# controller_v4.net
KiCad netlist of a schematic drawn in EAGLE
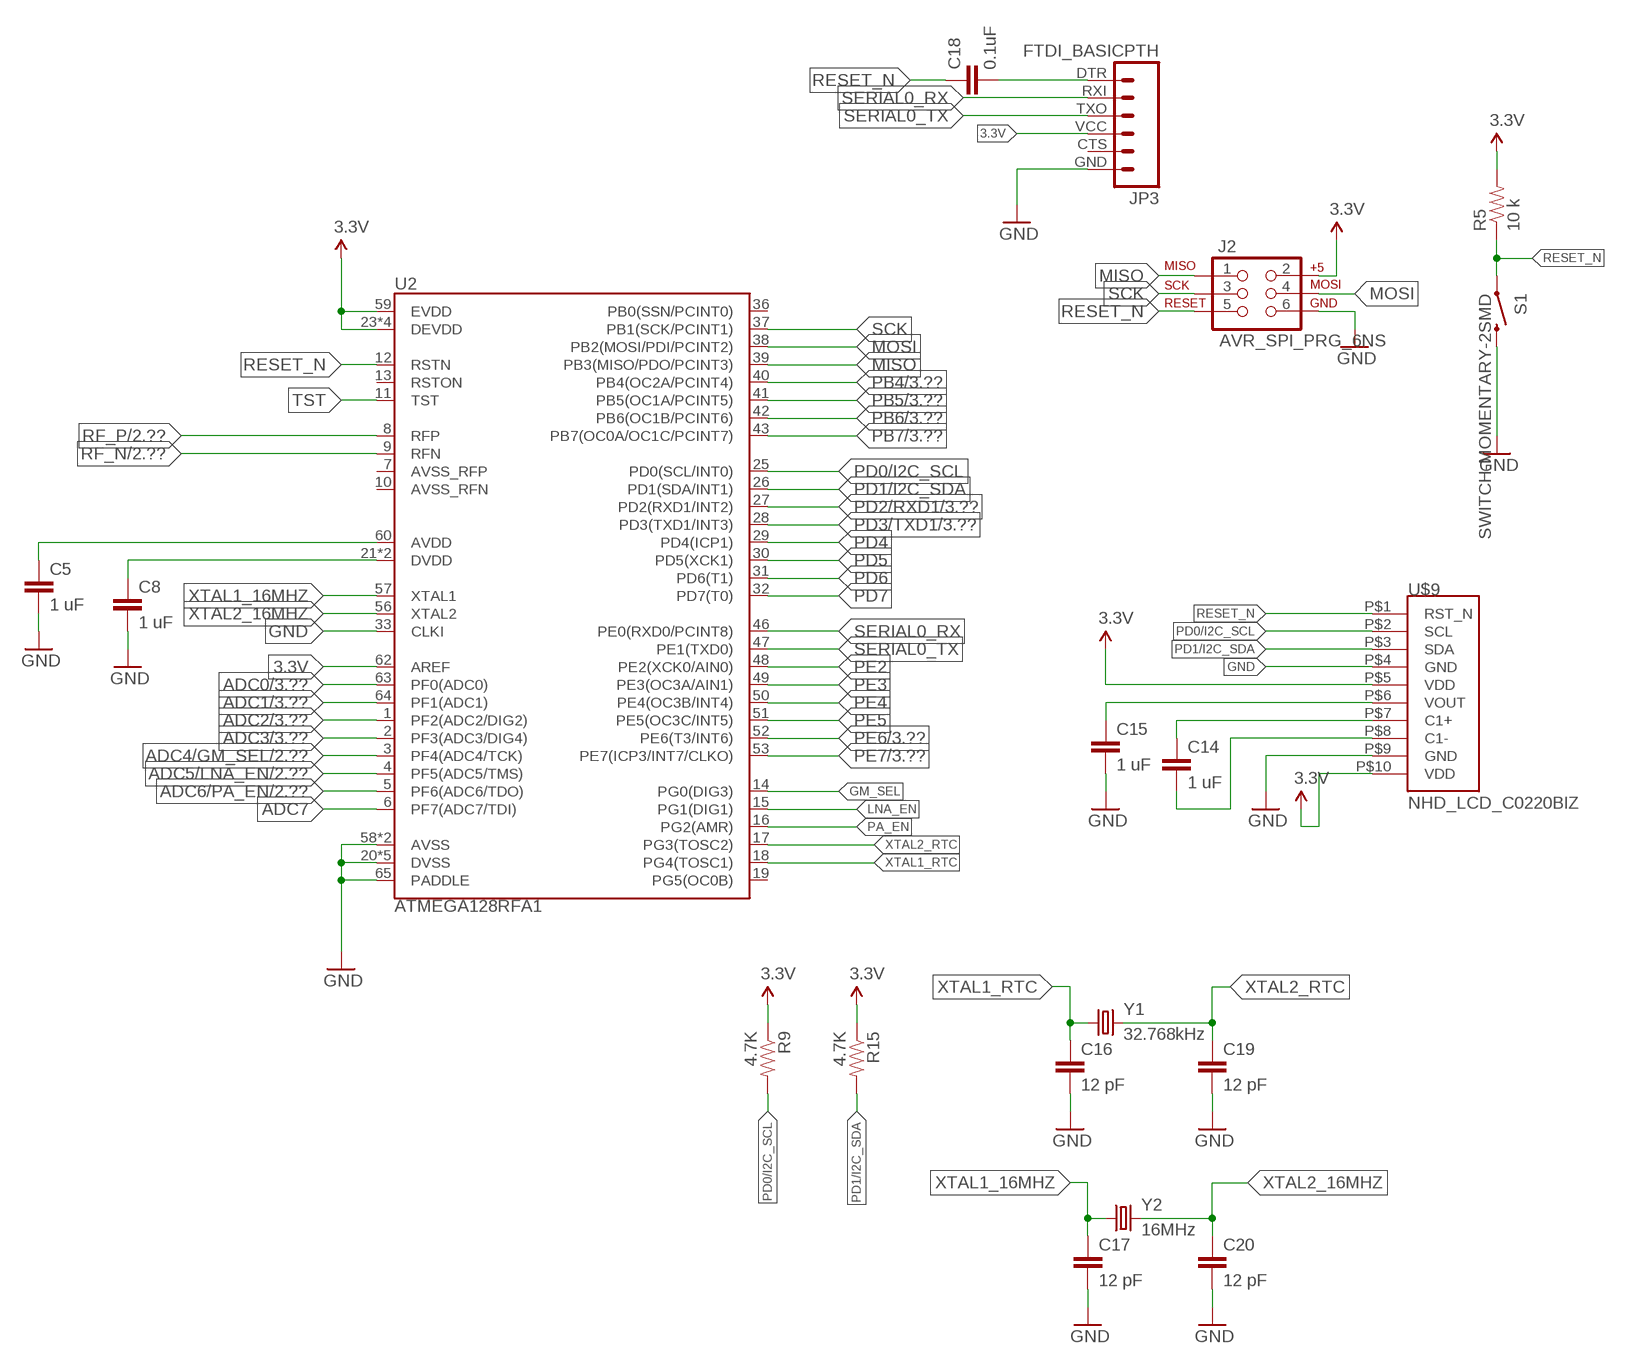
[diagram p0: schematic, sheet 1]
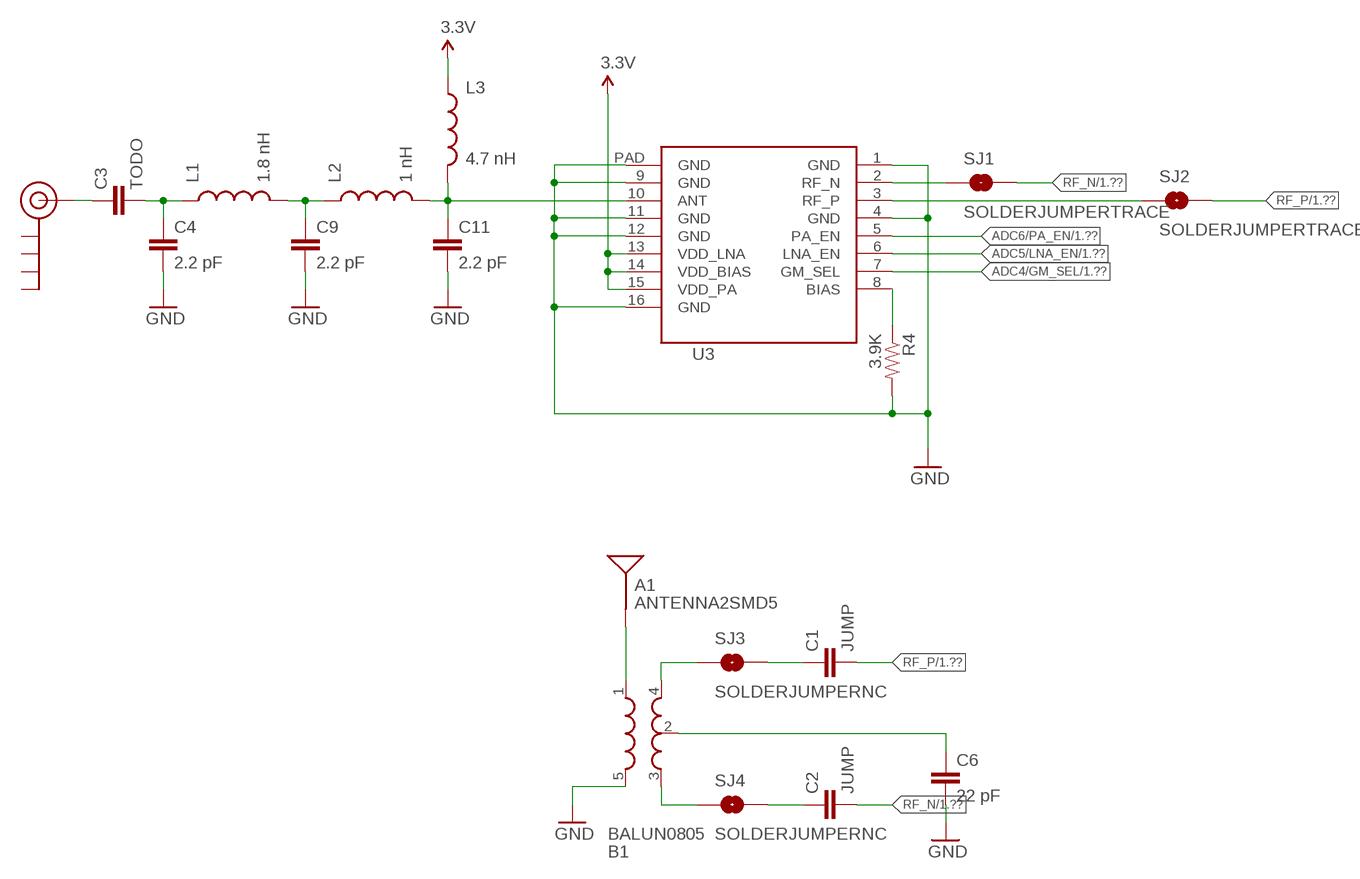
[diagram p1: schematic, sheet 2]
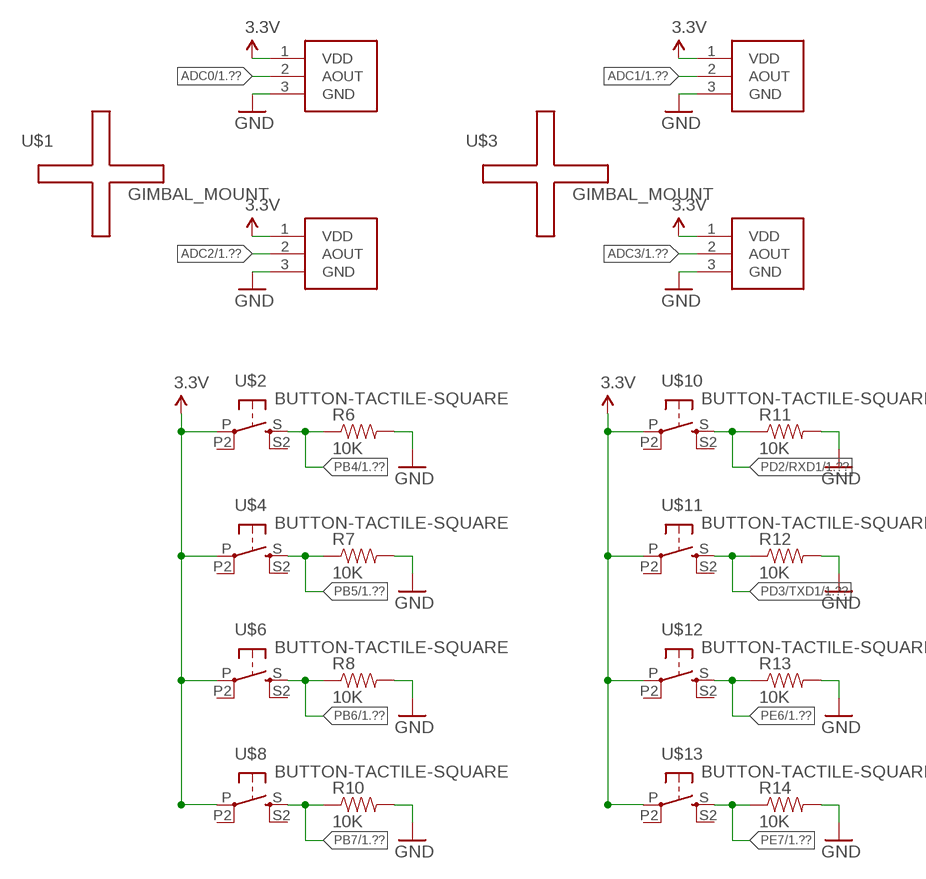
[diagram p2: schematic, sheet 3]
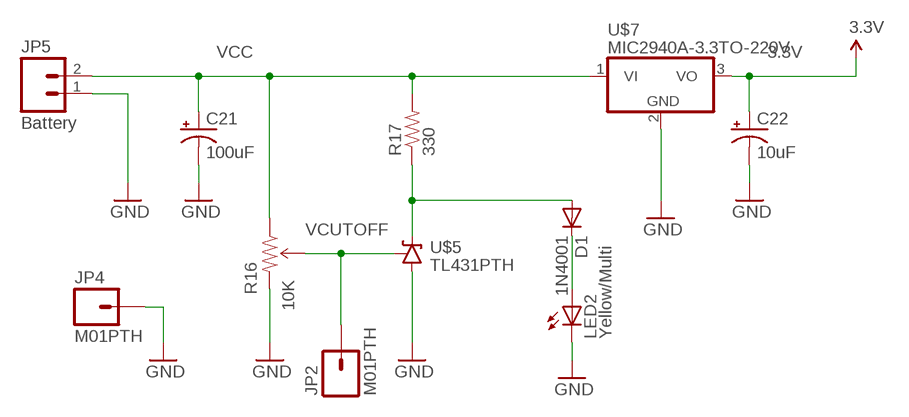
[diagram p3: schematic, sheet 4]

(export (version "E")
  (design (tool "Eeschema 10.0.6"))
  (components
    (comp (ref "A1")
      (value "ANTENNA2SMD5")
      (footprint "eagle-import:ANTENNA-CHIP5")
      (libsource (lib "eagle-import") (part "ANTENNA2SMD5"))
    )
    (comp (ref "B1")
      (value "BALUN0805")
      (footprint "eagle-import:BALUN")
      (libsource (lib "eagle-import") (part "BALUN0805"))
    )
    (comp (ref "C1")
      (value "JUMP")
      (footprint "eagle-import:0805")
      (libsource (lib "eagle-import") (part "CAP0805"))
    )
    (comp (ref "C2")
      (value "JUMP")
      (footprint "eagle-import:0805")
      (libsource (lib "eagle-import") (part "CAP0805"))
    )
    (comp (ref "C3")
      (value "TODO")
      (footprint "eagle-import:0805")
      (libsource (lib "eagle-import") (part "CAP0805"))
    )
    (comp (ref "C4")
      (value "2.2 pF")
      (footprint "eagle-import:0805")
      (libsource (lib "eagle-import") (part "CAP0805"))
    )
    (comp (ref "C6")
      (value "22 pF")
      (footprint "eagle-import:0805")
      (libsource (lib "eagle-import") (part "CAP0805"))
    )
    (comp (ref "C9")
      (value "2.2 pF")
      (footprint "eagle-import:0805")
      (libsource (lib "eagle-import") (part "CAP0805"))
    )
    (comp (ref "C11")
      (value "2.2 pF")
      (footprint "eagle-import:0805")
      (libsource (lib "eagle-import") (part "CAP0805"))
    )
    (comp (ref "J$1")
      (value "SMA_EDGE")
      (footprint "eagle-import:SMA-EDGE")
      (libsource (lib "eagle-import") (part "SMA_EDGE"))
    )
    (comp (ref "L1")
      (value "1.8 nH")
      (footprint "eagle-import:0805")
      (libsource (lib "eagle-import") (part "INDUCTOR0805"))
    )
    (comp (ref "L2")
      (value "1 nH")
      (footprint "eagle-import:0805")
      (libsource (lib "eagle-import") (part "INDUCTOR0805"))
    )
    (comp (ref "L3")
      (value "4.7 nH")
      (footprint "eagle-import:0805")
      (libsource (lib "eagle-import") (part "INDUCTOR0805"))
    )
    (comp (ref "R4")
      (value "3.9K")
      (footprint "eagle-import:0805")
      (libsource (lib "eagle-import") (part "RESISTOR0805-RES"))
    )
    (comp (ref "SJ1")
      (value "SOLDERJUMPERTRACE")
      (footprint "eagle-import:SJ_2S-TRACE")
      (libsource (lib "eagle-import") (part "SOLDERJUMPERTRACE"))
    )
    (comp (ref "SJ2")
      (value "SOLDERJUMPERTRACE")
      (footprint "eagle-import:SJ_2S-TRACE")
      (libsource (lib "eagle-import") (part "SOLDERJUMPERTRACE"))
    )
    (comp (ref "SJ3")
      (value "SOLDERJUMPERNC")
      (footprint "eagle-import:SJ_2S")
      (libsource (lib "eagle-import") (part "SOLDERJUMPERNC"))
    )
    (comp (ref "SJ4")
      (value "SOLDERJUMPERNC")
      (footprint "eagle-import:SJ_2S")
      (libsource (lib "eagle-import") (part "SOLDERJUMPERNC"))
    )
    (comp (ref "U3")
      (value "RF_AMPLIFIER")
      (footprint "eagle-import:QFN65P400X400X100-17N")
      (libsource (lib "eagle-import") (part "CC2592QF"))
    )
    (comp (ref "C21")
      (value "100uF")
      (footprint "eagle-import:E3,5-8")
      (libsource (lib "eagle-import") (part "CPOL-USE3.5-8"))
    )
    (comp (ref "C22")
      (value "10uF")
      (footprint "eagle-import:E2,5-5")
      (libsource (lib "eagle-import") (part "CPOL-USE2.5-5"))
    )
    (comp (ref "D1")
      (value "1N4001")
      (footprint "eagle-import:DO41-10")
      (libsource (lib "eagle-import") (part "1N4004"))
    )
    (comp (ref "JP2")
      (value "M01PTH")
      (footprint "eagle-import:1X01")
      (libsource (lib "eagle-import") (part "M01PTH"))
    )
    (comp (ref "JP4")
      (value "M01PTH")
      (footprint "eagle-import:1X01")
      (libsource (lib "eagle-import") (part "M01PTH"))
    )
    (comp (ref "JP5")
      (value "Battery")
      (footprint "eagle-import:1X02")
      (libsource (lib "eagle-import") (part "M02PTH"))
    )
    (comp (ref "LED2")
      (value "Yellow/Multi")
      (footprint "eagle-import:LED5MM")
      (libsource (lib "eagle-import") (part "LED5MM"))
    )
    (comp (ref "R16")
      (value "10K")
      (footprint "eagle-import:3386U")
      (libsource (lib "eagle-import") (part "TRIMPOT-PTH-KNOB"))
    )
    (comp (ref "R17")
      (value "330")
      (footprint "eagle-import:AXIAL-0.3")
      (libsource (lib "eagle-import") (part "SparkFun_RESISTORAXIAL-0.3"))
    )
    (comp (ref "U$5")
      (value "TL431PTH")
      (footprint "eagle-import:TO-92")
      (libsource (lib "eagle-import") (part "TL431PTH"))
    )
    (comp (ref "U$7")
      (value "MIC2940A-3.3TO-220V")
      (footprint "eagle-import:TO-220V")
      (libsource (lib "eagle-import") (part "MIC2940A-3.3TO-220V"))
    )
    (comp (ref "J3")
      (value "GIMBAL_3PIN")
      (footprint "eagle-import:JST-3-PTH")
      (libsource (lib "eagle-import") (part "GIMBAL_3PIN"))
    )
    (comp (ref "J4")
      (value "GIMBAL_3PIN")
      (footprint "eagle-import:JST-3-PTH")
      (libsource (lib "eagle-import") (part "GIMBAL_3PIN"))
    )
    (comp (ref "J5")
      (value "GIMBAL_3PIN")
      (footprint "eagle-import:JST-3-PTH")
      (libsource (lib "eagle-import") (part "GIMBAL_3PIN"))
    )
    (comp (ref "J6")
      (value "GIMBAL_3PIN")
      (footprint "eagle-import:JST-3-PTH")
      (libsource (lib "eagle-import") (part "GIMBAL_3PIN"))
    )
    (comp (ref "R6")
      (value "10K")
      (footprint "eagle-import:0805")
      (libsource (lib "eagle-import") (part "RESISTOR0805-RES"))
    )
    (comp (ref "R7")
      (value "10K")
      (footprint "eagle-import:0805")
      (libsource (lib "eagle-import") (part "RESISTOR0805-RES"))
    )
    (comp (ref "R8")
      (value "10K")
      (footprint "eagle-import:0805")
      (libsource (lib "eagle-import") (part "RESISTOR0805-RES"))
    )
    (comp (ref "R10")
      (value "10K")
      (footprint "eagle-import:0805")
      (libsource (lib "eagle-import") (part "RESISTOR0805-RES"))
    )
    (comp (ref "R11")
      (value "10K")
      (footprint "eagle-import:0805")
      (libsource (lib "eagle-import") (part "RESISTOR0805-RES"))
    )
    (comp (ref "R12")
      (value "10K")
      (footprint "eagle-import:0805")
      (libsource (lib "eagle-import") (part "RESISTOR0805-RES"))
    )
    (comp (ref "R13")
      (value "10K")
      (footprint "eagle-import:0805")
      (libsource (lib "eagle-import") (part "RESISTOR0805-RES"))
    )
    (comp (ref "R14")
      (value "10K")
      (footprint "eagle-import:0805")
      (libsource (lib "eagle-import") (part "RESISTOR0805-RES"))
    )
    (comp (ref "U$1")
      (value "GIMBAL_MOUNT")
      (footprint "eagle-import:GIMBAL_FOOTPRINT")
      (libsource (lib "eagle-import") (part "GIMBAL_MOUNT"))
    )
    (comp (ref "U$2")
      (value "BUTTON-TACTILE-SQUARE")
      (footprint "eagle-import:BUTTON-TACTILE-SQUARE-ADAFRUIT1010")
      (libsource (lib "eagle-import") (part "BUTTON-TACTILE-SQUARE"))
    )
    (comp (ref "U$3")
      (value "GIMBAL_MOUNT")
      (footprint "eagle-import:GIMBAL_FOOTPRINT")
      (libsource (lib "eagle-import") (part "GIMBAL_MOUNT"))
    )
    (comp (ref "U$4")
      (value "BUTTON-TACTILE-SQUARE")
      (footprint "eagle-import:BUTTON-TACTILE-SQUARE-ADAFRUIT1010")
      (libsource (lib "eagle-import") (part "BUTTON-TACTILE-SQUARE"))
    )
    (comp (ref "U$6")
      (value "BUTTON-TACTILE-SQUARE")
      (footprint "eagle-import:BUTTON-TACTILE-SQUARE-ADAFRUIT1010")
      (libsource (lib "eagle-import") (part "BUTTON-TACTILE-SQUARE"))
    )
    (comp (ref "U$8")
      (value "BUTTON-TACTILE-SQUARE")
      (footprint "eagle-import:BUTTON-TACTILE-SQUARE-ADAFRUIT1010")
      (libsource (lib "eagle-import") (part "BUTTON-TACTILE-SQUARE"))
    )
    (comp (ref "U$10")
      (value "BUTTON-TACTILE-SQUARE")
      (footprint "eagle-import:BUTTON-TACTILE-SQUARE-ADAFRUIT1010")
      (libsource (lib "eagle-import") (part "BUTTON-TACTILE-SQUARE"))
    )
    (comp (ref "U$11")
      (value "BUTTON-TACTILE-SQUARE")
      (footprint "eagle-import:BUTTON-TACTILE-SQUARE-ADAFRUIT1010")
      (libsource (lib "eagle-import") (part "BUTTON-TACTILE-SQUARE"))
    )
    (comp (ref "U$12")
      (value "BUTTON-TACTILE-SQUARE")
      (footprint "eagle-import:BUTTON-TACTILE-SQUARE-ADAFRUIT1010")
      (libsource (lib "eagle-import") (part "BUTTON-TACTILE-SQUARE"))
    )
    (comp (ref "U$13")
      (value "BUTTON-TACTILE-SQUARE")
      (footprint "eagle-import:BUTTON-TACTILE-SQUARE-ADAFRUIT1010")
      (libsource (lib "eagle-import") (part "BUTTON-TACTILE-SQUARE"))
    )
    (comp (ref "C5")
      (value "1 uF")
      (footprint "eagle-import:0805")
      (libsource (lib "eagle-import") (part "CAP0805"))
    )
    (comp (ref "C8")
      (value "1 uF")
      (footprint "eagle-import:0805")
      (libsource (lib "eagle-import") (part "CAP0805"))
    )
    (comp (ref "C14")
      (value "1 uF")
      (footprint "eagle-import:0805")
      (libsource (lib "eagle-import") (part "CAP0805"))
    )
    (comp (ref "C15")
      (value "1 uF")
      (footprint "eagle-import:0805")
      (libsource (lib "eagle-import") (part "CAP0805"))
    )
    (comp (ref "C16")
      (value "12 pF")
      (footprint "eagle-import:0805")
      (libsource (lib "eagle-import") (part "CAP0805"))
    )
    (comp (ref "C17")
      (value "12 pF")
      (footprint "eagle-import:0805")
      (libsource (lib "eagle-import") (part "CAP0805"))
    )
    (comp (ref "C18")
      (value "0.1uF")
      (footprint "eagle-import:0805")
      (libsource (lib "eagle-import") (part "CAP0805"))
    )
    (comp (ref "C19")
      (value "12 pF")
      (footprint "eagle-import:0805")
      (libsource (lib "eagle-import") (part "CAP0805"))
    )
    (comp (ref "C20")
      (value "12 pF")
      (footprint "eagle-import:0805")
      (libsource (lib "eagle-import") (part "CAP0805"))
    )
    (comp (ref "J2")
      (value "AVR_SPI_PRG_6NS")
      (footprint "eagle-import:2X3-NS")
      (libsource (lib "eagle-import") (part "AVR_SPI_PRG_6NS"))
    )
    (comp (ref "JP3")
      (value "FTDI_BASICPTH")
      (footprint "eagle-import:FTDI_BASIC")
      (libsource (lib "eagle-import") (part "FTDI_BASICPTH"))
    )
    (comp (ref "R5")
      (value "10 k")
      (footprint "eagle-import:0805")
      (libsource (lib "eagle-import") (part "RESISTOR0805-RES"))
    )
    (comp (ref "R9")
      (value "4.7K")
      (footprint "eagle-import:0805")
      (libsource (lib "eagle-import") (part "RESISTOR0805-RES"))
    )
    (comp (ref "R15")
      (value "4.7K")
      (footprint "eagle-import:0805")
      (libsource (lib "eagle-import") (part "RESISTOR0805-RES"))
    )
    (comp (ref "S1")
      (value "SWITCH-MOMENTARY-2SMD")
      (footprint "eagle-import:TACTILE_SWITCH_SMD")
      (libsource (lib "eagle-import") (part "SWITCH-MOMENTARY-2SMD"))
    )
    (comp (ref "U$9")
      (value "NHD_LCD_C0220BIZ")
      (footprint "eagle-import:1X08-2MMPTH-LCD")
      (libsource (lib "eagle-import") (part "NHD_LCD_C0220BIZ"))
    )
    (comp (ref "U2")
      (value "ATMEGA128RFA1")
      (footprint "eagle-import:QFN-64")
      (libsource (lib "eagle-import") (part "ATMEGA128RFA1"))
    )
    (comp (ref "Y1")
      (value "32.768kHz")
      (footprint "eagle-import:CRYSTAL-32KHZ-SMD")
      (libsource (lib "eagle-import") (part "CRYSTAL32-SMD"))
    )
    (comp (ref "Y2")
      (value "16MHz")
      (footprint "eagle-import:CRYSTAL-SMD-5X3")
      (libsource (lib "eagle-import") (part "CRYSTAL5X3"))
    )
  )
  (nets
    (net (code "1") (name "3.3V") (class "Default")
      (node (ref "C22") (pin "+") (pinfunction "+_+") (pintype "passive"))
      (node (ref "J2") (pin "2") (pinfunction "2_2") (pintype "passive"))
      (node (ref "J3") (pin "1") (pinfunction "VDD_1") (pintype "power_in"))
      (node (ref "J4") (pin "1") (pinfunction "VDD_1") (pintype "power_in"))
      (node (ref "J5") (pin "1") (pinfunction "VDD_1") (pintype "power_in"))
      (node (ref "J6") (pin "1") (pinfunction "VDD_1") (pintype "power_in"))
      (node (ref "JP3") (pin "VCC") (pinfunction "4_VCC") (pintype "passive"))
      (node (ref "L3") (pin "1") (pinfunction "1_1") (pintype "passive"))
      (node (ref "R15") (pin "1") (pinfunction "1_1") (pintype "passive"))
      (node (ref "R5") (pin "2") (pinfunction "2_2") (pintype "passive"))
      (node (ref "R9") (pin "1") (pinfunction "1_1") (pintype "passive"))
      (node (ref "U$10") (pin "P") (pinfunction "P_P") (pintype "passive"))
      (node (ref "U$11") (pin "P") (pinfunction "P_P") (pintype "passive"))
      (node (ref "U$12") (pin "P") (pinfunction "P_P") (pintype "passive"))
      (node (ref "U$13") (pin "P") (pinfunction "P_P") (pintype "passive"))
      (node (ref "U$2") (pin "P") (pinfunction "P_P") (pintype "passive"))
      (node (ref "U$4") (pin "P") (pinfunction "P_P") (pintype "passive"))
      (node (ref "U$6") (pin "P") (pinfunction "P_P") (pintype "passive"))
      (node (ref "U$7") (pin "3") (pinfunction "VO_3") (pintype "passive"))
      (node (ref "U$8") (pin "P") (pinfunction "P_P") (pintype "passive"))
      (node (ref "U$9") (pin "P$10") (pinfunction "VDD_P$10") (pintype "bidirectional"))
      (node (ref "U$9") (pin "P$5") (pinfunction "VDD_P$5") (pintype "bidirectional"))
      (node (ref "U2") (pin "23") (pinfunction "DEVDD_23") (pintype "bidirectional"))
      (node (ref "U2") (pin "34") (pinfunction "DEVDD_34") (pintype "bidirectional"))
      (node (ref "U2") (pin "44") (pinfunction "DEVDD_44") (pintype "bidirectional"))
      (node (ref "U2") (pin "54") (pinfunction "DEVDD_54") (pintype "bidirectional"))
      (node (ref "U2") (pin "59") (pinfunction "EVDD_59") (pintype "bidirectional"))
      (node (ref "U2") (pin "62") (pinfunction "AREF_62") (pintype "bidirectional"))
      (node (ref "U3") (pin "13") (pinfunction "VDD_LNA_13") (pintype "power_in"))
      (node (ref "U3") (pin "14") (pinfunction "VDD_BIAS_14") (pintype "power_in"))
      (node (ref "U3") (pin "15") (pinfunction "VDD_PA_15") (pintype "power_in"))
    )
    (net (code "2") (name "ADC0") (class "Default")
      (node (ref "J6") (pin "2") (pinfunction "AOUT_2") (pintype "bidirectional"))
      (node (ref "U2") (pin "63") (pinfunction "PF0(ADC0)_63") (pintype "bidirectional"))
    )
    (net (code "3") (name "ADC1") (class "Default")
      (node (ref "J3") (pin "2") (pinfunction "AOUT_2") (pintype "bidirectional"))
      (node (ref "U2") (pin "64") (pinfunction "PF1(ADC1)_64") (pintype "bidirectional"))
    )
    (net (code "4") (name "ADC2") (class "Default")
      (node (ref "J5") (pin "2") (pinfunction "AOUT_2") (pintype "bidirectional"))
      (node (ref "U2") (pin "1") (pinfunction "PF2(ADC2/DIG2)_1") (pintype "bidirectional"))
    )
    (net (code "5") (name "ADC3") (class "Default")
      (node (ref "J4") (pin "2") (pinfunction "AOUT_2") (pintype "bidirectional"))
      (node (ref "U2") (pin "2") (pinfunction "PF3(ADC3/DIG4)_2") (pintype "bidirectional"))
    )
    (net (code "6") (name "ADC4{slash}GM_SEL") (class "Default")
      (node (ref "U2") (pin "3") (pinfunction "PF4(ADC4/TCK)_3") (pintype "bidirectional"))
      (node (ref "U3") (pin "7") (pinfunction "GM_SEL_7") (pintype "input"))
    )
    (net (code "7") (name "ADC5{slash}LNA_EN") (class "Default")
      (node (ref "U2") (pin "4") (pinfunction "PF5(ADC5/TMS)_4") (pintype "bidirectional"))
      (node (ref "U3") (pin "6") (pinfunction "LNA_EN_6") (pintype "input"))
    )
    (net (code "8") (name "ADC6{slash}PA_EN") (class "Default")
      (node (ref "U2") (pin "5") (pinfunction "PF6(ADC6/TDO)_5") (pintype "bidirectional"))
      (node (ref "U3") (pin "5") (pinfunction "PA_EN_5") (pintype "input"))
    )
    (net (code "9") (name "ADC7") (class "Default")
      (node (ref "U2") (pin "6") (pinfunction "PF7(ADC7/TDI)_6") (pintype "bidirectional"))
    )
    (net (code "10") (name "GM_SEL") (class "Default")
      (node (ref "U2") (pin "14") (pinfunction "PG0(DIG3)_14") (pintype "bidirectional"))
    )
    (net (code "11") (name "GND") (class "Default")
      (node (ref "B1") (pin "5") (pinfunction "GND_5") (pintype "bidirectional"))
      (node (ref "C11") (pin "2") (pinfunction "2_2") (pintype "passive"))
      (node (ref "C15") (pin "2") (pinfunction "2_2") (pintype "passive"))
      (node (ref "C16") (pin "2") (pinfunction "2_2") (pintype "passive"))
      (node (ref "C17") (pin "2") (pinfunction "2_2") (pintype "passive"))
      (node (ref "C19") (pin "2") (pinfunction "2_2") (pintype "passive"))
      (node (ref "C20") (pin "2") (pinfunction "2_2") (pintype "passive"))
      (node (ref "C21") (pin "-") (pinfunction "-_-") (pintype "passive"))
      (node (ref "C22") (pin "-") (pinfunction "-_-") (pintype "passive"))
      (node (ref "C4") (pin "2") (pinfunction "2_2") (pintype "passive"))
      (node (ref "C5") (pin "2") (pinfunction "2_2") (pintype "passive"))
      (node (ref "C6") (pin "2") (pinfunction "2_2") (pintype "passive"))
      (node (ref "C8") (pin "2") (pinfunction "2_2") (pintype "passive"))
      (node (ref "C9") (pin "2") (pinfunction "2_2") (pintype "passive"))
      (node (ref "J2") (pin "6") (pinfunction "6_6") (pintype "passive"))
      (node (ref "J3") (pin "3") (pinfunction "GND_3") (pintype "power_in"))
      (node (ref "J4") (pin "3") (pinfunction "GND_3") (pintype "power_in"))
      (node (ref "J5") (pin "3") (pinfunction "GND_3") (pintype "power_in"))
      (node (ref "J6") (pin "3") (pinfunction "GND_3") (pintype "power_in"))
      (node (ref "JP3") (pin "GND") (pinfunction "6_GND") (pintype "passive"))
      (node (ref "JP4") (pin "1") (pinfunction "1_1") (pintype "passive"))
      (node (ref "JP5") (pin "1") (pinfunction "1_1") (pintype "passive"))
      (node (ref "LED2") (pin "K") (pinfunction "C_K") (pintype "passive"))
      (node (ref "R10") (pin "2") (pinfunction "2_2") (pintype "passive"))
      (node (ref "R11") (pin "2") (pinfunction "2_2") (pintype "passive"))
      (node (ref "R12") (pin "2") (pinfunction "2_2") (pintype "passive"))
      (node (ref "R13") (pin "2") (pinfunction "2_2") (pintype "passive"))
      (node (ref "R14") (pin "2") (pinfunction "2_2") (pintype "passive"))
      (node (ref "R16") (pin "3") (pinfunction "CW_3") (pintype "passive"))
      (node (ref "R4") (pin "2") (pinfunction "2_2") (pintype "passive"))
      (node (ref "R6") (pin "2") (pinfunction "2_2") (pintype "passive"))
      (node (ref "R7") (pin "2") (pinfunction "2_2") (pintype "passive"))
      (node (ref "R8") (pin "2") (pinfunction "2_2") (pintype "passive"))
      (node (ref "S1") (pin "3") (pinfunction "2_3") (pintype "passive"))
      (node (ref "U$5") (pin "2") (pinfunction "A_2") (pintype "passive"))
      (node (ref "U$7") (pin "2") (pinfunction "GND_2") (pintype "passive"))
      (node (ref "U$9") (pin "P$4") (pinfunction "GND_P$4") (pintype "bidirectional"))
      (node (ref "U$9") (pin "P$9") (pinfunction "GND_P$9") (pintype "bidirectional"))
      (node (ref "U2") (pin "20") (pinfunction "DVSS_20") (pintype "bidirectional"))
      (node (ref "U2") (pin "24") (pinfunction "DVSS_24") (pintype "bidirectional"))
      (node (ref "U2") (pin "33") (pinfunction "CLKI_33") (pintype "bidirectional"))
      (node (ref "U2") (pin "35") (pinfunction "DVSS_35") (pintype "bidirectional"))
      (node (ref "U2") (pin "45") (pinfunction "DVSS_45") (pintype "bidirectional"))
      (node (ref "U2") (pin "55") (pinfunction "DVSS_55") (pintype "bidirectional"))
      (node (ref "U2") (pin "58") (pinfunction "AVSS_58") (pintype "bidirectional"))
      (node (ref "U2") (pin "61") (pinfunction "AVSS_61") (pintype "bidirectional"))
      (node (ref "U2") (pin "65") (pinfunction "PADDLE_65") (pintype "bidirectional"))
      (node (ref "U3") (pin "1") (pinfunction "GND_1") (pintype "power_in"))
      (node (ref "U3") (pin "11") (pinfunction "GND_11") (pintype "power_in"))
      (node (ref "U3") (pin "12") (pinfunction "GND_12") (pintype "power_in"))
      (node (ref "U3") (pin "16") (pinfunction "GND_16") (pintype "power_in"))
      (node (ref "U3") (pin "4") (pinfunction "GND_4") (pintype "power_in"))
      (node (ref "U3") (pin "9") (pinfunction "GND_9") (pintype "power_in"))
      (node (ref "U3") (pin "PAD") (pinfunction "GND_PAD") (pintype "power_in"))
    )
    (net (code "12") (name "LNA_EN") (class "Default")
      (node (ref "U2") (pin "15") (pinfunction "PG1(DIG1)_15") (pintype "bidirectional"))
    )
    (net (code "13") (name "MISO") (class "Default")
      (node (ref "J2") (pin "1") (pinfunction "1_1") (pintype "passive"))
      (node (ref "U2") (pin "39") (pinfunction "PB3(MISO/PDO/PCINT3)_39") (pintype "bidirectional"))
    )
    (net (code "14") (name "MOSI") (class "Default")
      (node (ref "J2") (pin "4") (pinfunction "4_4") (pintype "passive"))
      (node (ref "U2") (pin "38") (pinfunction "PB2(MOSI/PDI/PCINT2)_38") (pintype "bidirectional"))
    )
    (net (code "15") (name "Net-(A1-SIGNAL)") (class "Default")
      (node (ref "A1") (pin "FEED") (pinfunction "SIGNAL_FEED") (pintype "bidirectional"))
      (node (ref "B1") (pin "1") (pinfunction "IN_1") (pintype "bidirectional"))
    )
    (net (code "16") (name "Net-(B1-GND-Pad2)") (class "Default")
      (node (ref "B1") (pin "2") (pinfunction "GND_2") (pintype "bidirectional"))
      (node (ref "C6") (pin "1") (pinfunction "1_1") (pintype "passive"))
    )
    (net (code "17") (name "Net-(B1-OUT1)") (class "Default")
      (node (ref "B1") (pin "4") (pinfunction "OUT1_4") (pintype "bidirectional"))
      (node (ref "SJ3") (pin "1") (pinfunction "1_1") (pintype "passive"))
    )
    (net (code "18") (name "Net-(B1-OUT2)") (class "Default")
      (node (ref "B1") (pin "3") (pinfunction "OUT2_3") (pintype "bidirectional"))
      (node (ref "SJ4") (pin "1") (pinfunction "1_1") (pintype "passive"))
    )
    (net (code "19") (name "Net-(C1-Pad1)") (class "Default")
      (node (ref "C1") (pin "1") (pinfunction "1_1") (pintype "passive"))
      (node (ref "SJ3") (pin "2") (pinfunction "2_2") (pintype "passive"))
    )
    (net (code "20") (name "Net-(C2-Pad1)") (class "Default")
      (node (ref "C2") (pin "1") (pinfunction "1_1") (pintype "passive"))
      (node (ref "SJ4") (pin "2") (pinfunction "2_2") (pintype "passive"))
    )
    (net (code "21") (name "Net-(C3-Pad2)") (class "Default")
      (node (ref "C3") (pin "2") (pinfunction "2_2") (pintype "passive"))
      (node (ref "C4") (pin "1") (pinfunction "1_1") (pintype "passive"))
      (node (ref "L1") (pin "1") (pinfunction "1_1") (pintype "passive"))
    )
    (net (code "22") (name "Net-(C8-Pad1)") (class "Default")
      (node (ref "C8") (pin "1") (pinfunction "1_1") (pintype "passive"))
      (node (ref "U2") (pin "21") (pinfunction "DVDD_21") (pintype "bidirectional"))
      (node (ref "U2") (pin "22") (pinfunction "DVDD_22") (pintype "bidirectional"))
    )
    (net (code "23") (name "Net-(C9-Pad1)") (class "Default")
      (node (ref "C9") (pin "1") (pinfunction "1_1") (pintype "passive"))
      (node (ref "L1") (pin "2") (pinfunction "2_2") (pintype "passive"))
      (node (ref "L2") (pin "1") (pinfunction "1_1") (pintype "passive"))
    )
    (net (code "24") (name "Net-(D1-PadC)") (class "Default")
      (node (ref "D1") (pin "C") (pinfunction "C_C") (pintype "passive"))
      (node (ref "LED2") (pin "A") (pinfunction "A_A") (pintype "passive"))
    )
    (net (code "25") (name "Net-(J$1-SIGNAL)") (class "Default")
      (node (ref "C3") (pin "1") (pinfunction "1_1") (pintype "passive"))
      (node (ref "J$1") (pin "SIG") (pinfunction "SIGNAL_SIG") (pintype "bidirectional"))
    )
    (net (code "26") (name "Net-(JP3-1)") (class "Default")
      (node (ref "C18") (pin "2") (pinfunction "2_2") (pintype "passive"))
      (node (ref "JP3") (pin "DTR") (pinfunction "1_DTR") (pintype "passive"))
    )
    (net (code "27") (name "Net-(R17-1)") (class "Default")
      (node (ref "D1") (pin "A") (pinfunction "A_A") (pintype "passive"))
      (node (ref "R17") (pin "P$1") (pinfunction "1_P$1") (pintype "passive"))
      (node (ref "U$5") (pin "3") (pinfunction "C_3") (pintype "passive"))
    )
    (net (code "28") (name "Net-(U$9-C1+)") (class "Default")
      (node (ref "C14") (pin "1") (pinfunction "1_1") (pintype "passive"))
      (node (ref "U$9") (pin "P$7") (pinfunction "C1+_P$7") (pintype "bidirectional"))
    )
    (net (code "29") (name "Net-(U$9-C1-)") (class "Default")
      (node (ref "C14") (pin "2") (pinfunction "2_2") (pintype "passive"))
      (node (ref "U$9") (pin "P$8") (pinfunction "C1-_P$8") (pintype "bidirectional"))
    )
    (net (code "30") (name "Net-(U$9-VOUT)") (class "Default")
      (node (ref "C15") (pin "1") (pinfunction "1_1") (pintype "passive"))
      (node (ref "U$9") (pin "P$6") (pinfunction "VOUT_P$6") (pintype "bidirectional"))
    )
    (net (code "31") (name "Net-(U2-AVDD)") (class "Default")
      (node (ref "C5") (pin "1") (pinfunction "1_1") (pintype "passive"))
      (node (ref "U2") (pin "60") (pinfunction "AVDD_60") (pintype "bidirectional"))
    )
    (net (code "32") (name "Net-(U3-ANT)") (class "Default")
      (node (ref "C11") (pin "1") (pinfunction "1_1") (pintype "passive"))
      (node (ref "L2") (pin "2") (pinfunction "2_2") (pintype "passive"))
      (node (ref "L3") (pin "2") (pinfunction "2_2") (pintype "passive"))
      (node (ref "U3") (pin "10") (pinfunction "ANT_10") (pintype "bidirectional"))
    )
    (net (code "33") (name "Net-(U3-BIAS)") (class "Default")
      (node (ref "R4") (pin "1") (pinfunction "1_1") (pintype "passive"))
      (node (ref "U3") (pin "8") (pinfunction "BIAS_8") (pintype "passive"))
    )
    (net (code "34") (name "Net-(U3-RF_N)") (class "Default")
      (node (ref "SJ1") (pin "1") (pinfunction "1_1") (pintype "passive"))
      (node (ref "U3") (pin "2") (pinfunction "RF_N_2") (pintype "bidirectional"))
    )
    (net (code "35") (name "Net-(U3-RF_P)") (class "Default")
      (node (ref "SJ2") (pin "1") (pinfunction "1_1") (pintype "passive"))
      (node (ref "U3") (pin "3") (pinfunction "RF_P_3") (pintype "bidirectional"))
    )
    (net (code "36") (name "PA_EN") (class "Default")
      (node (ref "U2") (pin "16") (pinfunction "PG2(AMR)_16") (pintype "bidirectional"))
    )
    (net (code "37") (name "PB4") (class "Default")
      (node (ref "R6") (pin "1") (pinfunction "1_1") (pintype "passive"))
      (node (ref "U$2") (pin "S") (pinfunction "S_S") (pintype "passive"))
      (node (ref "U2") (pin "40") (pinfunction "PB4(OC2A/PCINT4)_40") (pintype "bidirectional"))
    )
    (net (code "38") (name "PB5") (class "Default")
      (node (ref "R7") (pin "1") (pinfunction "1_1") (pintype "passive"))
      (node (ref "U$4") (pin "S") (pinfunction "S_S") (pintype "passive"))
      (node (ref "U2") (pin "41") (pinfunction "PB5(OC1A/PCINT5)_41") (pintype "bidirectional"))
    )
    (net (code "39") (name "PB6") (class "Default")
      (node (ref "R8") (pin "1") (pinfunction "1_1") (pintype "passive"))
      (node (ref "U$6") (pin "S") (pinfunction "S_S") (pintype "passive"))
      (node (ref "U2") (pin "42") (pinfunction "PB6(OC1B/PCINT6)_42") (pintype "bidirectional"))
    )
    (net (code "40") (name "PB7") (class "Default")
      (node (ref "R10") (pin "1") (pinfunction "1_1") (pintype "passive"))
      (node (ref "U$8") (pin "S") (pinfunction "S_S") (pintype "passive"))
      (node (ref "U2") (pin "43") (pinfunction "PB7(OC0A/OC1C/PCINT7)_43") (pintype "bidirectional"))
    )
    (net (code "41") (name "PD0{slash}I2C_SCL") (class "Default")
      (node (ref "R9") (pin "2") (pinfunction "2_2") (pintype "passive"))
      (node (ref "U$9") (pin "P$2") (pinfunction "SCL_P$2") (pintype "bidirectional"))
      (node (ref "U2") (pin "25") (pinfunction "PD0(SCL/INT0)_25") (pintype "bidirectional"))
    )
    (net (code "42") (name "PD1{slash}I2C_SDA") (class "Default")
      (node (ref "R15") (pin "2") (pinfunction "2_2") (pintype "passive"))
      (node (ref "U$9") (pin "P$3") (pinfunction "SDA_P$3") (pintype "bidirectional"))
      (node (ref "U2") (pin "26") (pinfunction "PD1(SDA/INT1)_26") (pintype "bidirectional"))
    )
    (net (code "43") (name "PD2{slash}RXD1") (class "Default")
      (node (ref "R11") (pin "1") (pinfunction "1_1") (pintype "passive"))
      (node (ref "U$10") (pin "S") (pinfunction "S_S") (pintype "passive"))
      (node (ref "U2") (pin "27") (pinfunction "PD2(RXD1/INT2)_27") (pintype "bidirectional"))
    )
    (net (code "44") (name "PD3{slash}TXD1") (class "Default")
      (node (ref "R12") (pin "1") (pinfunction "1_1") (pintype "passive"))
      (node (ref "U$11") (pin "S") (pinfunction "S_S") (pintype "passive"))
      (node (ref "U2") (pin "28") (pinfunction "PD3(TXD1/INT3)_28") (pintype "bidirectional"))
    )
    (net (code "45") (name "PD4") (class "Default")
      (node (ref "U2") (pin "29") (pinfunction "PD4(ICP1)_29") (pintype "bidirectional"))
    )
    (net (code "46") (name "PD5") (class "Default")
      (node (ref "U2") (pin "30") (pinfunction "PD5(XCK1)_30") (pintype "bidirectional"))
    )
    (net (code "47") (name "PD6") (class "Default")
      (node (ref "U2") (pin "31") (pinfunction "PD6(T1)_31") (pintype "bidirectional"))
    )
    (net (code "48") (name "PD7") (class "Default")
      (node (ref "U2") (pin "32") (pinfunction "PD7(T0)_32") (pintype "bidirectional"))
    )
    (net (code "49") (name "PE2") (class "Default")
      (node (ref "U2") (pin "48") (pinfunction "PE2(XCK0/AIN0)_48") (pintype "bidirectional"))
    )
    (net (code "50") (name "PE3") (class "Default")
      (node (ref "U2") (pin "49") (pinfunction "PE3(OC3A/AIN1)_49") (pintype "bidirectional"))
    )
    (net (code "51") (name "PE4") (class "Default")
      (node (ref "U2") (pin "50") (pinfunction "PE4(OC3B/INT4)_50") (pintype "bidirectional"))
    )
    (net (code "52") (name "PE5") (class "Default")
      (node (ref "U2") (pin "51") (pinfunction "PE5(OC3C/INT5)_51") (pintype "bidirectional"))
    )
    (net (code "53") (name "PE6") (class "Default")
      (node (ref "R13") (pin "1") (pinfunction "1_1") (pintype "passive"))
      (node (ref "U$12") (pin "S") (pinfunction "S_S") (pintype "passive"))
      (node (ref "U2") (pin "52") (pinfunction "PE6(T3/INT6)_52") (pintype "bidirectional"))
    )
    (net (code "54") (name "PE7") (class "Default")
      (node (ref "R14") (pin "1") (pinfunction "1_1") (pintype "passive"))
      (node (ref "U$13") (pin "S") (pinfunction "S_S") (pintype "passive"))
      (node (ref "U2") (pin "53") (pinfunction "PE7(ICP3/INT7/CLKO)_53") (pintype "bidirectional"))
    )
    (net (code "55") (name "RESET_N") (class "Default")
      (node (ref "C18") (pin "1") (pinfunction "1_1") (pintype "passive"))
      (node (ref "J2") (pin "5") (pinfunction "5_5") (pintype "passive"))
      (node (ref "R5") (pin "1") (pinfunction "1_1") (pintype "passive"))
      (node (ref "S1") (pin "1") (pinfunction "1_1") (pintype "passive"))
      (node (ref "U$9") (pin "P$1") (pinfunction "RST_N_P$1") (pintype "bidirectional"))
      (node (ref "U2") (pin "12") (pinfunction "RSTN_12") (pintype "bidirectional"))
    )
    (net (code "56") (name "RF_N") (class "Default")
      (node (ref "C2") (pin "2") (pinfunction "2_2") (pintype "passive"))
      (node (ref "SJ1") (pin "2") (pinfunction "2_2") (pintype "passive"))
      (node (ref "U2") (pin "9") (pinfunction "RFN_9") (pintype "bidirectional"))
    )
    (net (code "57") (name "RF_P") (class "Default")
      (node (ref "C1") (pin "2") (pinfunction "2_2") (pintype "passive"))
      (node (ref "SJ2") (pin "2") (pinfunction "2_2") (pintype "passive"))
      (node (ref "U2") (pin "8") (pinfunction "RFP_8") (pintype "bidirectional"))
    )
    (net (code "58") (name "SCK") (class "Default")
      (node (ref "J2") (pin "3") (pinfunction "3_3") (pintype "passive"))
      (node (ref "U2") (pin "37") (pinfunction "PB1(SCK/PCINT1)_37") (pintype "bidirectional"))
    )
    (net (code "59") (name "SERIAL0_RX") (class "Default")
      (node (ref "JP3") (pin "RXI") (pinfunction "2_RXI") (pintype "passive"))
      (node (ref "U2") (pin "46") (pinfunction "PE0(RXD0/PCINT8)_46") (pintype "bidirectional"))
    )
    (net (code "60") (name "SERIAL0_TX") (class "Default")
      (node (ref "JP3") (pin "TXO") (pinfunction "3_TXO") (pintype "passive"))
      (node (ref "U2") (pin "47") (pinfunction "PE1(TXD0)_47") (pintype "bidirectional"))
    )
    (net (code "61") (name "TST") (class "Default")
      (node (ref "U2") (pin "11") (pinfunction "TST_11") (pintype "bidirectional"))
    )
    (net (code "62") (name "VCC") (class "Default")
      (node (ref "C21") (pin "+") (pinfunction "+_+") (pintype "passive"))
      (node (ref "JP5") (pin "2") (pinfunction "2_2") (pintype "passive"))
      (node (ref "R16") (pin "1") (pinfunction "CCW_1") (pintype "passive"))
      (node (ref "R17") (pin "P$2") (pinfunction "2_P$2") (pintype "passive"))
      (node (ref "U$7") (pin "1") (pinfunction "VI_1") (pintype "input"))
    )
    (net (code "63") (name "VCUTOFF") (class "Default")
      (node (ref "JP2") (pin "1") (pinfunction "1_1") (pintype "passive"))
      (node (ref "R16") (pin "2") (pinfunction "WIPER_2") (pintype "passive"))
      (node (ref "U$5") (pin "1") (pinfunction "R_1") (pintype "bidirectional"))
    )
    (net (code "64") (name "XTAL1_16MHZ") (class "Default")
      (node (ref "C17") (pin "1") (pinfunction "1_1") (pintype "passive"))
      (node (ref "U2") (pin "57") (pinfunction "XTAL1_57") (pintype "bidirectional"))
      (node (ref "Y2") (pin "1") (pinfunction "1_1") (pintype "passive"))
    )
    (net (code "65") (name "XTAL1_RTC") (class "Default")
      (node (ref "C16") (pin "1") (pinfunction "1_1") (pintype "passive"))
      (node (ref "U2") (pin "18") (pinfunction "PG4(TOSC1)_18") (pintype "bidirectional"))
      (node (ref "Y1") (pin "X1") (pinfunction "1_X1") (pintype "passive"))
    )
    (net (code "66") (name "XTAL2_16MHZ") (class "Default")
      (node (ref "C20") (pin "1") (pinfunction "1_1") (pintype "passive"))
      (node (ref "U2") (pin "56") (pinfunction "XTAL2_56") (pintype "bidirectional"))
      (node (ref "Y2") (pin "3") (pinfunction "2_3") (pintype "passive"))
    )
    (net (code "67") (name "XTAL2_RTC") (class "Default")
      (node (ref "C19") (pin "1") (pinfunction "1_1") (pintype "passive"))
      (node (ref "U2") (pin "17") (pinfunction "PG3(TOSC2)_17") (pintype "bidirectional"))
      (node (ref "Y1") (pin "X2") (pinfunction "2_X2") (pintype "passive"))
    )
    (net (code "68") (name "unconnected-(J$1-GND-PadGND@0)") (class "Default")
      (node (ref "J$1") (pin "GND@0") (pinfunction "GND_GND@0") (pintype "bidirectional"))
    )
    (net (code "69") (name "unconnected-(J$1-GND-PadGND@1)") (class "Default")
      (node (ref "J$1") (pin "GND@1") (pinfunction "GND_GND@1") (pintype "bidirectional"))
    )
    (net (code "70") (name "unconnected-(J$1-GND-PadGND@2)") (class "Default")
      (node (ref "J$1") (pin "GND@2") (pinfunction "GND_GND@2") (pintype "bidirectional"))
    )
    (net (code "71") (name "unconnected-(J$1-GND-PadGND@3)") (class "Default")
      (node (ref "J$1") (pin "GND@3") (pinfunction "GND_GND@3") (pintype "bidirectional"))
    )
    (net (code "72") (name "unconnected-(JP3-5-PadCTS)") (class "Default")
      (node (ref "JP3") (pin "CTS") (pinfunction "5_CTS") (pintype "passive"))
    )
    (net (code "73") (name "unconnected-(U$2-P1-PadP2)") (class "Default")
      (node (ref "U$2") (pin "P2") (pinfunction "P1_P2") (pintype "passive"))
    )
    (net (code "74") (name "unconnected-(U$2-S1-PadS2)") (class "Default")
      (node (ref "U$2") (pin "S2") (pinfunction "S1_S2") (pintype "passive"))
    )
    (net (code "75") (name "unconnected-(U$4-P1-PadP2)") (class "Default")
      (node (ref "U$4") (pin "P2") (pinfunction "P1_P2") (pintype "passive"))
    )
    (net (code "76") (name "unconnected-(U$4-S1-PadS2)") (class "Default")
      (node (ref "U$4") (pin "S2") (pinfunction "S1_S2") (pintype "passive"))
    )
    (net (code "77") (name "unconnected-(U$6-P1-PadP2)") (class "Default")
      (node (ref "U$6") (pin "P2") (pinfunction "P1_P2") (pintype "passive"))
    )
    (net (code "78") (name "unconnected-(U$6-S1-PadS2)") (class "Default")
      (node (ref "U$6") (pin "S2") (pinfunction "S1_S2") (pintype "passive"))
    )
    (net (code "79") (name "unconnected-(U$8-P1-PadP2)") (class "Default")
      (node (ref "U$8") (pin "P2") (pinfunction "P1_P2") (pintype "passive"))
    )
    (net (code "80") (name "unconnected-(U$8-S1-PadS2)") (class "Default")
      (node (ref "U$8") (pin "S2") (pinfunction "S1_S2") (pintype "passive"))
    )
    (net (code "81") (name "unconnected-(U$10-P1-PadP2)") (class "Default")
      (node (ref "U$10") (pin "P2") (pinfunction "P1_P2") (pintype "passive"))
    )
    (net (code "82") (name "unconnected-(U$10-S1-PadS2)") (class "Default")
      (node (ref "U$10") (pin "S2") (pinfunction "S1_S2") (pintype "passive"))
    )
    (net (code "83") (name "unconnected-(U$11-P1-PadP2)") (class "Default")
      (node (ref "U$11") (pin "P2") (pinfunction "P1_P2") (pintype "passive"))
    )
    (net (code "84") (name "unconnected-(U$11-S1-PadS2)") (class "Default")
      (node (ref "U$11") (pin "S2") (pinfunction "S1_S2") (pintype "passive"))
    )
    (net (code "85") (name "unconnected-(U$12-P1-PadP2)") (class "Default")
      (node (ref "U$12") (pin "P2") (pinfunction "P1_P2") (pintype "passive"))
    )
    (net (code "86") (name "unconnected-(U$12-S1-PadS2)") (class "Default")
      (node (ref "U$12") (pin "S2") (pinfunction "S1_S2") (pintype "passive"))
    )
    (net (code "87") (name "unconnected-(U$13-P1-PadP2)") (class "Default")
      (node (ref "U$13") (pin "P2") (pinfunction "P1_P2") (pintype "passive"))
    )
    (net (code "88") (name "unconnected-(U$13-S1-PadS2)") (class "Default")
      (node (ref "U$13") (pin "S2") (pinfunction "S1_S2") (pintype "passive"))
    )
    (net (code "89") (name "unconnected-(U2-AVSS_RFN-Pad10)") (class "Default")
      (node (ref "U2") (pin "10") (pinfunction "AVSS_RFN_10") (pintype "bidirectional"))
    )
    (net (code "90") (name "unconnected-(U2-AVSS_RFP-Pad7)") (class "Default")
      (node (ref "U2") (pin "7") (pinfunction "AVSS_RFP_7") (pintype "bidirectional"))
    )
    (net (code "91") (name "unconnected-(U2-PB0(SSN{slash}PCINT0)-Pad36)") (class "Default")
      (node (ref "U2") (pin "36") (pinfunction "PB0(SSN/PCINT0)_36") (pintype "bidirectional"))
    )
    (net (code "92") (name "unconnected-(U2-PG5(OC0B)-Pad19)") (class "Default")
      (node (ref "U2") (pin "19") (pinfunction "PG5(OC0B)_19") (pintype "bidirectional"))
    )
    (net (code "93") (name "unconnected-(U2-RSTON-Pad13)") (class "Default")
      (node (ref "U2") (pin "13") (pinfunction "RSTON_13") (pintype "bidirectional"))
    )
  )
)
